# SchBTRC.net
KiCad netlist of a schematic drawn in Altium Designer
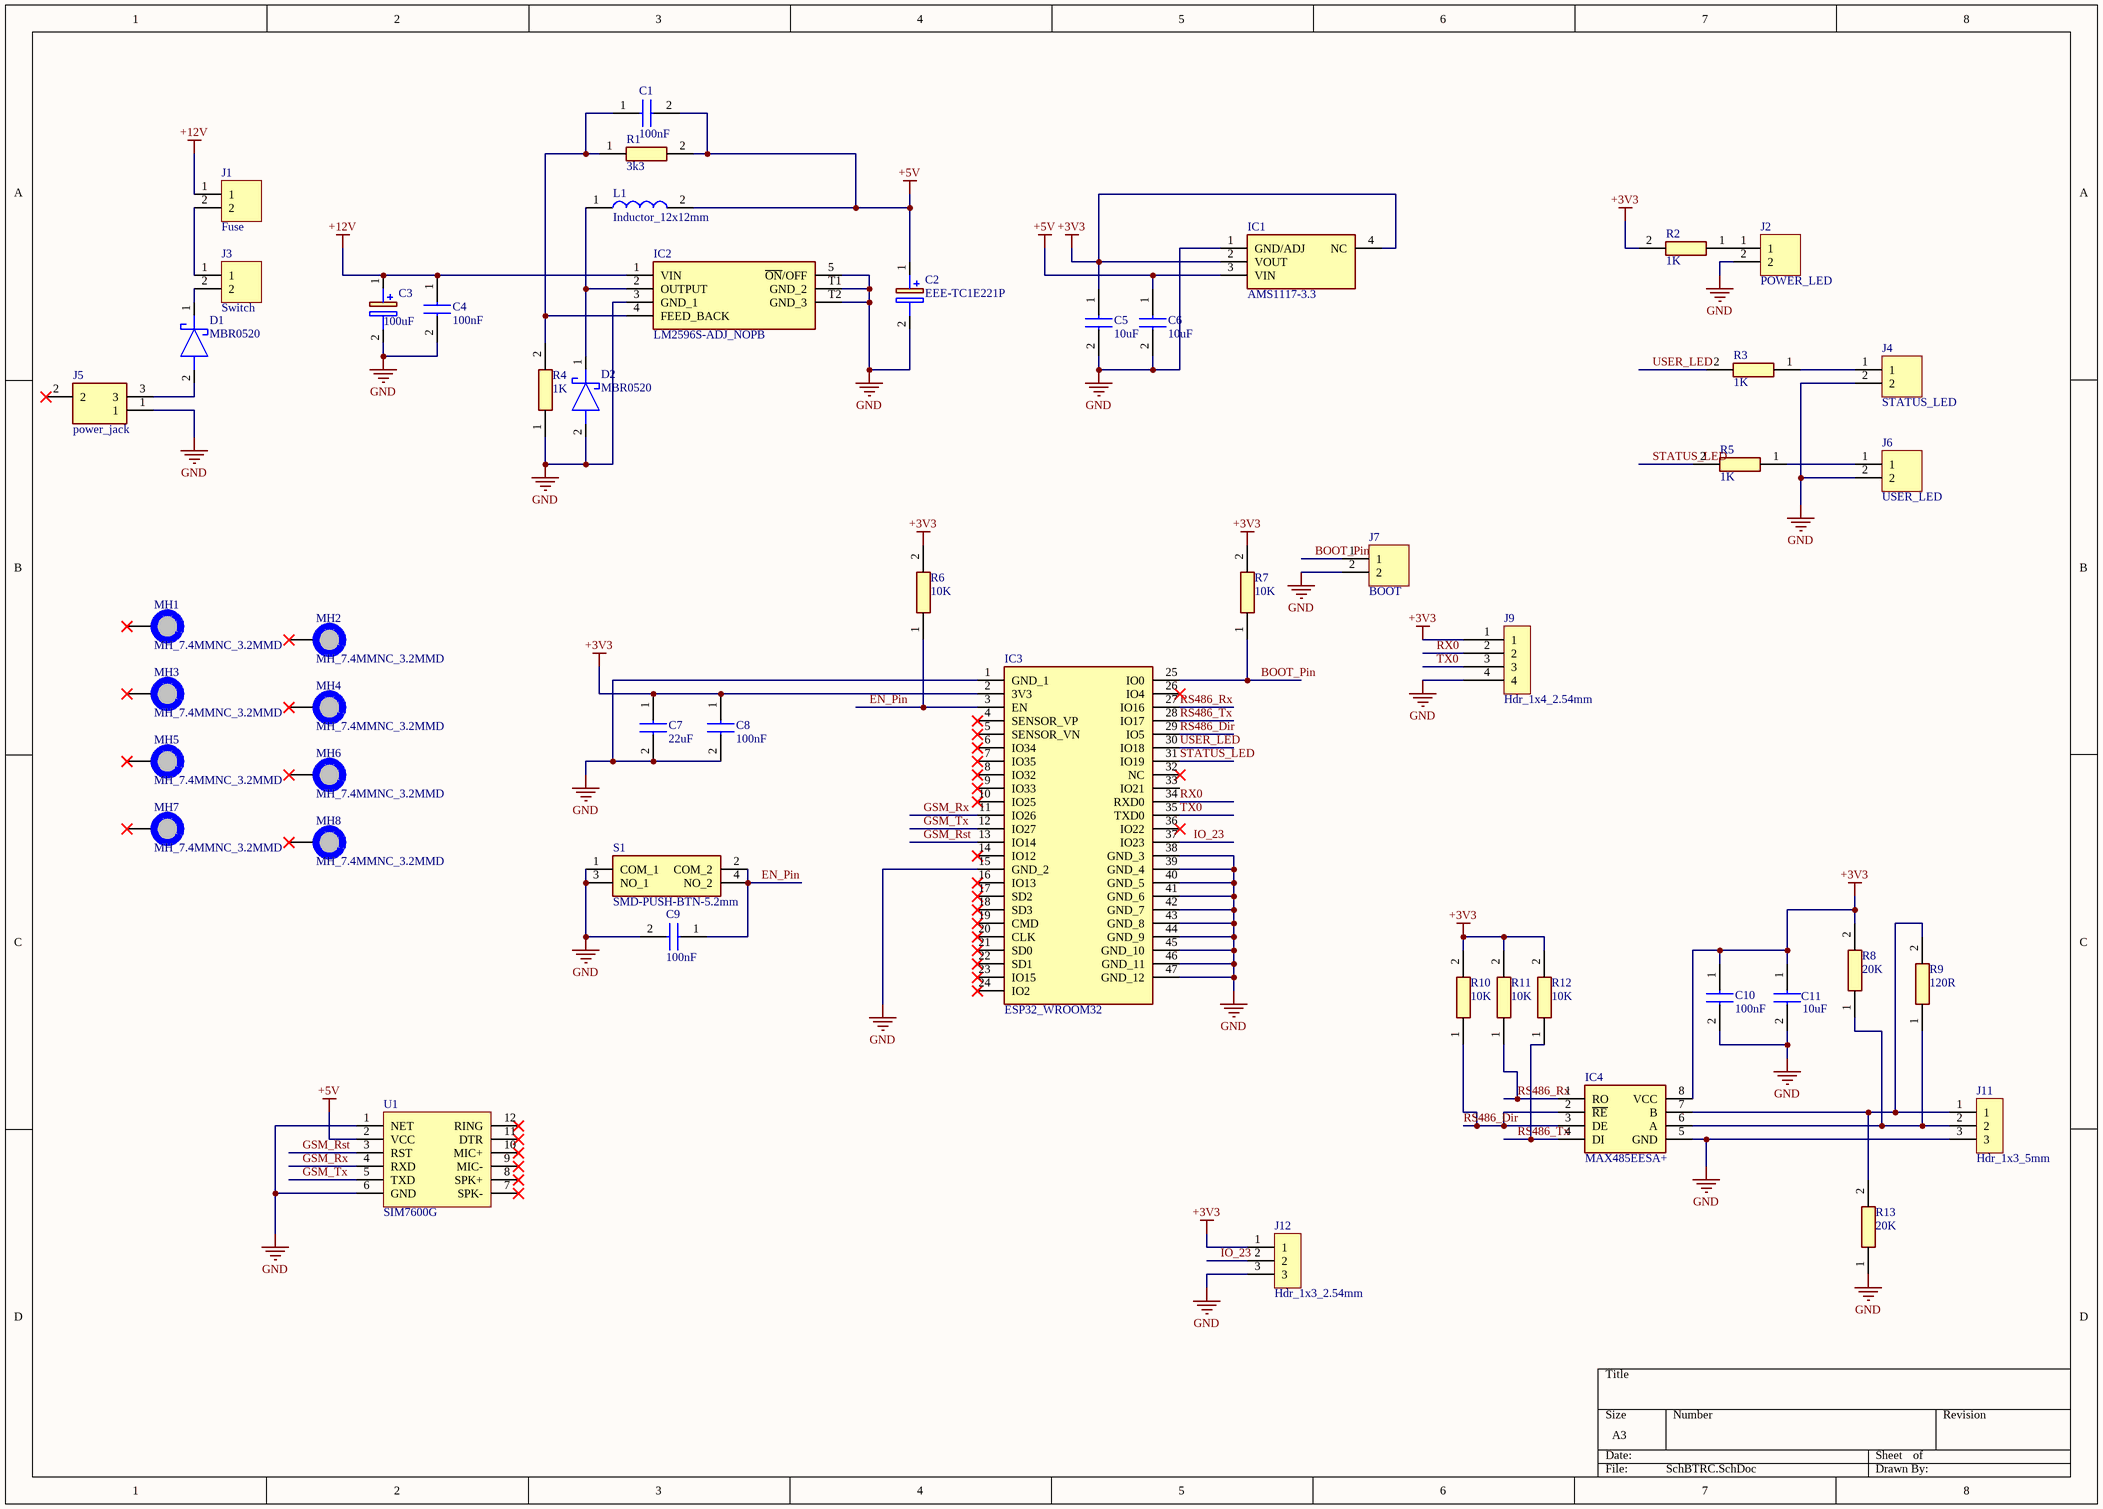
[diagram p0: SchBTRC.SchDoc]

(export (version "E")
  (design (tool "Eeschema 10.0.6"))
  (components
    (comp (ref "C1")
      (value "100nF")
      (footprint "CAPC3216X100N")
      (description "Capacitor")
      (fields
        (field (name "MANUFACTURER_PART_NUMBER") "C3216X5R1C106K085AC")
        (field (name "MOUSER PART NUMBER") "810-C3216X5R1C106K0C")
      )
      (libsource (lib "SchlibBTRC") (part "C3216X5R1C106K085AC"))
    )
    (comp (ref "C2")
      (value "EEE-TC1E221P")
      (footprint "PcbLibBTRC:EEE0JA152UAP")
      (description "Capacitor Polarised")
      (fields (field (name "MOUSER PART NUMBER") "667-EEE-TC1E221P"))
      (libsource (lib "*") (part "EEE-TC1E221P"))
    )
    (comp (ref "C3")
      (value "100uF")
      (footprint "PcbLibBTRC:EEE0JA331XP")
      (description "Capacitor Polarised")
      (fields
        (field (name "MANUFACTURER_PART_NUMBER") "EEE-TC1C101XP")
        (field (name "MOUSER PART NUMBER") "667-EEE-TC1C101XP")
      )
      (libsource (lib "*") (part "EEE-TC1C101XP"))
    )
    (comp (ref "C4")
      (value "100nF")
      (footprint "CAPC3216X100N")
      (description "Capacitor")
      (fields
        (field (name "MANUFACTURER_PART_NUMBER") "C3216X5R1C106K085AC")
        (field (name "MOUSER PART NUMBER") "810-C3216X5R1C106K0C")
      )
      (libsource (lib "SchlibBTRC") (part "C3216X5R1C106K085AC"))
    )
    (comp (ref "C5")
      (value "10uF")
      (footprint "CAPC3216X100N")
      (description "Capacitor")
      (fields
        (field (name "MANUFACTURER_PART_NUMBER") "C3216X5R1C106K085AC")
        (field (name "MOUSER PART NUMBER") "810-C3216X5R1C106K0C")
      )
      (libsource (lib "SchlibBTRC") (part "C3216X5R1C106K085AC"))
    )
    (comp (ref "C6")
      (value "10uF")
      (footprint "CAPC3216X100N")
      (description "Capacitor")
      (fields
        (field (name "MANUFACTURER_PART_NUMBER") "C3216X5R1C106K085AC")
        (field (name "MOUSER PART NUMBER") "810-C3216X5R1C106K0C")
      )
      (libsource (lib "SchlibBTRC") (part "C3216X5R1C106K085AC"))
    )
    (comp (ref "C7")
      (value "22uF")
      (footprint "CAPC3216X100N")
      (description "Capacitor")
      (fields
        (field (name "MANUFACTURER_PART_NUMBER") "C3216X5R1C106K085AC")
        (field (name "MOUSER PART NUMBER") "810-C3216X5R1C106K0C")
      )
      (libsource (lib "SchlibBTRC") (part "C3216X5R1C106K085AC"))
    )
    (comp (ref "C8")
      (value "100nF")
      (footprint "CAPC3216X100N")
      (description "Capacitor")
      (fields
        (field (name "MANUFACTURER_PART_NUMBER") "C3216X5R1C106K085AC")
        (field (name "MOUSER PART NUMBER") "810-C3216X5R1C106K0C")
      )
      (libsource (lib "SchlibBTRC") (part "C3216X5R1C106K085AC"))
    )
    (comp (ref "C9")
      (value "100nF")
      (footprint "CAPC3216X100N")
      (description "Capacitor")
      (fields
        (field (name "MANUFACTURER_PART_NUMBER") "C3216X5R1C106K085AC")
        (field (name "MOUSER PART NUMBER") "810-C3216X5R1C106K0C")
      )
      (libsource (lib "SchlibBTRC") (part "C3216X5R1C106K085AC"))
    )
    (comp (ref "C10")
      (value "100nF")
      (footprint "CAPC3216X100N")
      (description "Capacitor")
      (fields
        (field (name "MANUFACTURER_PART_NUMBER") "C3216X5R1C106K085AC")
        (field (name "MOUSER PART NUMBER") "810-C3216X5R1C106K0C")
      )
      (libsource (lib "SchlibBTRC") (part "C3216X5R1C106K085AC"))
    )
    (comp (ref "C11")
      (value "10uF")
      (footprint "CAPC3216X100N")
      (description "Capacitor")
      (fields
        (field (name "MANUFACTURER_PART_NUMBER") "C3216X5R1C106K085AC")
        (field (name "MOUSER PART NUMBER") "810-C3216X5R1C106K0C")
      )
      (libsource (lib "SchlibBTRC") (part "C3216X5R1C106K085AC"))
    )
    (comp (ref "D1")
      (value "MBR0520")
      (footprint "PcbLibBTRC:SOD3716X120N")
      (description "Schottky Diode")
      (libsource (lib "*") (part "MBR0520"))
    )
    (comp (ref "D2")
      (value "MBR0520")
      (footprint "PcbLibBTRC:SOD3716X120N")
      (description "Schottky Diode")
      (libsource (lib "*") (part "MBR0520"))
    )
    (comp (ref "IC1")
      (value "AMS1117-3.3")
      (footprint "PcbLibBTRC:SOT229P700X180-4N")
      (description "Integrated Circuit")
      (libsource (lib "*") (part "AMS1117-3.3"))
    )
    (comp (ref "IC2")
      (value "LM2596S-ADJ_NOPB")
      (footprint "PcbLibBTRC:LM2596SXADJ")
      (description "Integrated Circuit")
      (fields
        (field (name "MANUFACTURER_PART_NUMBER") "LM2596S-ADJ/NOPB")
        (field (name "MOUSER PART NUMBER") "926-LM2596S-ADJ/NOPB")
      )
      (libsource (lib "*") (part "LM2596S-ADJ_NOPB"))
    )
    (comp (ref "IC3")
      (value "ESP32_WROOM32")
      (footprint "PcbLibBTRC:ESP32WROOM32")
      (description "Integrated Circuit")
      (fields (field (name "MANUFACTURER_PART_NUMBER") "ESP32 WROOM32"))
      (libsource (lib "*") (part "ESP32_WROOM32"))
    )
    (comp (ref "IC4")
      (value "MAX485EESA+")
      (footprint "PcbLibBTRC:SOIC127P600X175-8N")
      (description "Integrated Circuit")
      (fields (field (name "MOUSER PART NUMBER") "700-MAX485EESA"))
      (libsource (lib "*") (part "MAX485EESA+"))
    )
    (comp (ref "J1")
      (value "Fuse")
      (footprint "HDR_1x2_2.54mm")
      (libsource (lib "SchlibBTRC") (part "Hdr_1x2_2.54mm"))
    )
    (comp (ref "J2")
      (value "POWER_LED")
      (footprint "HDR_1x2_2.54mm")
      (libsource (lib "SchlibBTRC") (part "Hdr_1x2_2.54mm"))
    )
    (comp (ref "J3")
      (value "Switch")
      (footprint "HDR_1x2_2.54mm")
      (libsource (lib "SchlibBTRC") (part "Hdr_1x2_2.54mm"))
    )
    (comp (ref "J4")
      (value "STATUS_LED")
      (footprint "HDR_1x2_2.54mm")
      (libsource (lib "SchlibBTRC") (part "Hdr_1x2_2.54mm"))
    )
    (comp (ref "J5")
      (value "power_jack")
      (footprint "power_jack")
      (description "Connector")
      (fields (field (name "MANUFACTURER_PART_NUMBER") "1613 20"))
      (libsource (lib "SchlibBTRC") (part "power_jack"))
    )
    (comp (ref "J6")
      (value "USER_LED")
      (footprint "HDR_1x2_2.54mm")
      (libsource (lib "SchlibBTRC") (part "Hdr_1x2_2.54mm"))
    )
    (comp (ref "J7")
      (value "BOOT")
      (footprint "HDR_1x2_2.54mm")
      (libsource (lib "SchlibBTRC") (part "Hdr_1x2_2.54mm"))
    )
    (comp (ref "J9")
      (value "Hdr_1x4_2.54mm")
      (footprint "Hdr_1x4_2.54mm")
      (libsource (lib "SchlibBTRC") (part "Hdr_1x4_2.54mm"))
    )
    (comp (ref "J11")
      (value "Hdr_1x3_5mm")
      (footprint "Hdr_1x3_5.0mm")
      (libsource (lib "SchlibBTRC") (part "Hdr_1x3_5mm"))
    )
    (comp (ref "J12")
      (value "Hdr_1x3_2.54mm")
      (footprint "Hdr_1x3_2.54mm")
      (libsource (lib "SchlibBTRC") (part "Hdr_1x3_2.54mm"))
    )
    (comp (ref "L1")
      (value "Inductor_12x12mm")
      (footprint "Inductor_12x12mm")
      (description "Inductor")
      (fields
        (field (name "MANUFACTURER_PART_NUMBER") "744774147")
        (field (name "MOUSER PART NUMBER") "710-744774147")
      )
      (libsource (lib "SchlibBTRC") (part "Inductor_12x12mm"))
    )
    (comp (ref "MH1")
      (value "MH_7.4MMNC_3.2MMD")
      (footprint "MH_7.4MMNC_3.2MMD_NON_COPPER_NPTH")
      (libsource (lib "SchlibBTRC") (part "MH_7.4MMNC_3.2MMD"))
    )
    (comp (ref "MH2")
      (value "MH_7.4MMNC_3.2MMD")
      (footprint "MH_7.4MMNC_3.2MMD_NON_COPPER_NPTH")
      (libsource (lib "SchlibBTRC") (part "MH_7.4MMNC_3.2MMD"))
    )
    (comp (ref "MH3")
      (value "MH_7.4MMNC_3.2MMD")
      (footprint "MH_7.4MMNC_3.2MMD_NON_COPPER_NPTH")
      (libsource (lib "SchlibBTRC") (part "MH_7.4MMNC_3.2MMD"))
    )
    (comp (ref "MH4")
      (value "MH_7.4MMNC_3.2MMD")
      (footprint "MH_7.4MMNC_3.2MMD_NON_COPPER_NPTH")
      (libsource (lib "SchlibBTRC") (part "MH_7.4MMNC_3.2MMD"))
    )
    (comp (ref "MH5")
      (value "MH_7.4MMNC_3.2MMD")
      (footprint "MH_7.4MMNC_3.2MMD_NON_COPPER_NPTH")
      (libsource (lib "SchlibBTRC") (part "MH_7.4MMNC_3.2MMD"))
    )
    (comp (ref "MH6")
      (value "MH_7.4MMNC_3.2MMD")
      (footprint "MH_7.4MMNC_3.2MMD_NON_COPPER_NPTH")
      (libsource (lib "SchlibBTRC") (part "MH_7.4MMNC_3.2MMD"))
    )
    (comp (ref "MH7")
      (value "MH_7.4MMNC_3.2MMD")
      (footprint "MH_7.4MMNC_3.2MMD_NON_COPPER_NPTH")
      (libsource (lib "SchlibBTRC") (part "MH_7.4MMNC_3.2MMD"))
    )
    (comp (ref "MH8")
      (value "MH_7.4MMNC_3.2MMD")
      (footprint "MH_7.4MMNC_3.2MMD_NON_COPPER_NPTH")
      (libsource (lib "SchlibBTRC") (part "MH_7.4MMNC_3.2MMD"))
    )
    (comp (ref "R1")
      (value "3k3")
      (footprint "RESC3216X75N")
      (description "Resistor")
      (fields
        (field (name "MANUFACTURER_PART_NUMBER") "CR1206-F/-2R00ELF")
        (field (name "MOUSER PART NUMBER") "652-CR1206-F/2R00ELF")
      )
      (libsource (lib "") (part "CR1206-F_-2R00ELF_2"))
    )
    (comp (ref "R2")
      (value "1K")
      (footprint "RESC3216X75N")
      (description "Resistor")
      (fields
        (field (name "MANUFACTURER_PART_NUMBER") "CR1206-F/-2R00ELF")
        (field (name "MOUSER PART NUMBER") "652-CR1206-F/2R00ELF")
      )
      (libsource (lib "") (part "CR1206-F_-2R00ELF_1"))
    )
    (comp (ref "R3")
      (value "1K")
      (footprint "RESC3216X75N")
      (description "Resistor")
      (fields
        (field (name "MANUFACTURER_PART_NUMBER") "CR1206-F/-2R00ELF")
        (field (name "MOUSER PART NUMBER") "652-CR1206-F/2R00ELF")
      )
      (libsource (lib "") (part "CR1206-F_-2R00ELF_1"))
    )
    (comp (ref "R4")
      (value "1K")
      (footprint "RESC3216X75N")
      (description "Resistor")
      (fields
        (field (name "MANUFACTURER_PART_NUMBER") "CR1206-F/-2R00ELF")
        (field (name "MOUSER PART NUMBER") "652-CR1206-F/2R00ELF")
      )
      (libsource (lib "SchlibBTRC") (part "CR1206-F_-2R00ELF"))
    )
    (comp (ref "R5")
      (value "1K")
      (footprint "RESC3216X75N")
      (description "Resistor")
      (fields
        (field (name "MANUFACTURER_PART_NUMBER") "CR1206-F/-2R00ELF")
        (field (name "MOUSER PART NUMBER") "652-CR1206-F/2R00ELF")
      )
      (libsource (lib "") (part "CR1206-F_-2R00ELF_1"))
    )
    (comp (ref "R6")
      (value "10K")
      (footprint "RESC3216X75N")
      (description "Resistor")
      (fields
        (field (name "MANUFACTURER_PART_NUMBER") "CR1206-F/-2R00ELF")
        (field (name "MOUSER PART NUMBER") "652-CR1206-F/2R00ELF")
      )
      (libsource (lib "SchlibBTRC") (part "CR1206-F_-2R00ELF"))
    )
    (comp (ref "R7")
      (value "10K")
      (footprint "RESC3216X75N")
      (description "Resistor")
      (fields
        (field (name "MANUFACTURER_PART_NUMBER") "CR1206-F/-2R00ELF")
        (field (name "MOUSER PART NUMBER") "652-CR1206-F/2R00ELF")
      )
      (libsource (lib "SchlibBTRC") (part "CR1206-F_-2R00ELF"))
    )
    (comp (ref "R8")
      (value "20K")
      (footprint "RESC3216X75N")
      (description "Resistor")
      (fields
        (field (name "MANUFACTURER_PART_NUMBER") "CR1206-F/-2R00ELF")
        (field (name "MOUSER PART NUMBER") "652-CR1206-F/2R00ELF")
      )
      (libsource (lib "SchlibBTRC") (part "CR1206-F_-2R00ELF"))
    )
    (comp (ref "R9")
      (value "120R")
      (footprint "RESC3216X75N")
      (description "Resistor")
      (fields
        (field (name "MANUFACTURER_PART_NUMBER") "CR1206-F/-2R00ELF")
        (field (name "MOUSER PART NUMBER") "652-CR1206-F/2R00ELF")
      )
      (libsource (lib "SchlibBTRC") (part "CR1206-F_-2R00ELF"))
    )
    (comp (ref "R10")
      (value "10K")
      (footprint "RESC3216X75N")
      (description "Resistor")
      (fields
        (field (name "MANUFACTURER_PART_NUMBER") "CR1206-F/-2R00ELF")
        (field (name "MOUSER PART NUMBER") "652-CR1206-F/2R00ELF")
      )
      (libsource (lib "SchlibBTRC") (part "CR1206-F_-2R00ELF"))
    )
    (comp (ref "R11")
      (value "10K")
      (footprint "RESC3216X75N")
      (description "Resistor")
      (fields
        (field (name "MANUFACTURER_PART_NUMBER") "CR1206-F/-2R00ELF")
        (field (name "MOUSER PART NUMBER") "652-CR1206-F/2R00ELF")
      )
      (libsource (lib "SchlibBTRC") (part "CR1206-F_-2R00ELF"))
    )
    (comp (ref "R12")
      (value "10K")
      (footprint "RESC3216X75N")
      (description "Resistor")
      (fields
        (field (name "MANUFACTURER_PART_NUMBER") "CR1206-F/-2R00ELF")
        (field (name "MOUSER PART NUMBER") "652-CR1206-F/2R00ELF")
      )
      (libsource (lib "SchlibBTRC") (part "CR1206-F_-2R00ELF"))
    )
    (comp (ref "R13")
      (value "20K")
      (footprint "RESC3216X75N")
      (description "Resistor")
      (fields
        (field (name "MANUFACTURER_PART_NUMBER") "CR1206-F/-2R00ELF")
        (field (name "MOUSER PART NUMBER") "652-CR1206-F/2R00ELF")
      )
      (libsource (lib "SchlibBTRC") (part "CR1206-F_-2R00ELF"))
    )
    (comp (ref "S1")
      (value "SMD-PUSH-BTN-5.2mm")
      (footprint "SMS_PUSH_BTN_5.2x5.2mm")
      (description "Switch")
      (fields
        (field (name "MANUFACTURER_PART_NUMBER") "COM-08720")
        (field (name "MOUSER PART NUMBER") "474-COM-08720")
      )
      (libsource (lib "SchlibBTRC") (part "SMD-PUSH-BTN-5.2mm"))
    )
    (comp (ref "U1")
      (value "SIM7600G")
      (footprint "SIM7600G_Module")
      (libsource (lib "SchlibBTRC") (part "SIM7600G_Module"))
    )
  )
  (nets
    (net (code "1") (name "+3V3") (class "Default")
      (node (ref "C10") (pin "1") (pinfunction "1_1") (pintype "passive"))
      (node (ref "C11") (pin "1") (pinfunction "1_1") (pintype "passive"))
      (node (ref "C5") (pin "1") (pinfunction "1_1") (pintype "passive"))
      (node (ref "C7") (pin "1") (pinfunction "1_1") (pintype "passive"))
      (node (ref "C8") (pin "1") (pinfunction "1_1") (pintype "passive"))
      (node (ref "IC1") (pin "2") (pinfunction "VOUT_2") (pintype "passive"))
      (node (ref "IC1") (pin "4") (pinfunction "NC_4") (pintype "passive"))
      (node (ref "IC3") (pin "2") (pinfunction "3V3_2") (pintype "passive"))
      (node (ref "IC4") (pin "8") (pinfunction "VCC_8") (pintype "passive"))
      (node (ref "J12") (pin "1") (pinfunction "1_1") (pintype "passive"))
      (node (ref "J9") (pin "1") (pinfunction "1_1") (pintype "passive"))
      (node (ref "R10") (pin "2") (pinfunction "2_2") (pintype "passive"))
      (node (ref "R11") (pin "2") (pinfunction "2_2") (pintype "passive"))
      (node (ref "R12") (pin "2") (pinfunction "2_2") (pintype "passive"))
      (node (ref "R2") (pin "2") (pinfunction "2_2") (pintype "passive"))
      (node (ref "R6") (pin "2") (pinfunction "2_2") (pintype "passive"))
      (node (ref "R7") (pin "2") (pinfunction "2_2") (pintype "passive"))
      (node (ref "R8") (pin "2") (pinfunction "2_2") (pintype "passive"))
    )
    (net (code "2") (name "+5V") (class "Default")
      (node (ref "C1") (pin "2") (pinfunction "2_2") (pintype "passive"))
      (node (ref "C2") (pin "1") (pinfunction "+_1") (pintype "passive"))
      (node (ref "C6") (pin "1") (pinfunction "1_1") (pintype "passive"))
      (node (ref "IC1") (pin "3") (pinfunction "VIN_3") (pintype "passive"))
      (node (ref "L1") (pin "2") (pinfunction "2_2") (pintype "passive"))
      (node (ref "R1") (pin "2") (pinfunction "2_2") (pintype "passive"))
      (node (ref "U1") (pin "2") (pinfunction "VCC_2") (pintype "passive"))
    )
    (net (code "3") (name "+12V") (class "Default")
      (node (ref "C3") (pin "1") (pinfunction "+_1") (pintype "passive"))
      (node (ref "C4") (pin "1") (pinfunction "1_1") (pintype "passive"))
      (node (ref "IC2") (pin "1") (pinfunction "VIN_1") (pintype "passive"))
      (node (ref "J1") (pin "1") (pinfunction "1_1") (pintype "passive"))
    )
    (net (code "4") (name "/BOOT_Pin") (class "Default")
      (node (ref "IC3") (pin "25") (pinfunction "IO0_25") (pintype "passive"))
      (node (ref "J7") (pin "1") (pinfunction "1_1") (pintype "passive"))
      (node (ref "R7") (pin "1") (pinfunction "1_1") (pintype "passive"))
    )
    (net (code "5") (name "/EN_Pin") (class "Default")
      (node (ref "C9") (pin "1") (pinfunction "1_1") (pintype "passive"))
      (node (ref "IC3") (pin "3") (pinfunction "EN_3") (pintype "passive"))
      (node (ref "R6") (pin "1") (pinfunction "1_1") (pintype "passive"))
      (node (ref "S1") (pin "2") (pinfunction "COM_2_2") (pintype "passive"))
      (node (ref "S1") (pin "4") (pinfunction "NO_2_4") (pintype "passive"))
    )
    (net (code "6") (name "/GSM_Rst") (class "Default")
      (node (ref "IC3") (pin "13") (pinfunction "IO14_13") (pintype "passive"))
      (node (ref "U1") (pin "3") (pinfunction "RST_3") (pintype "passive"))
    )
    (net (code "7") (name "/GSM_Rx") (class "Default")
      (node (ref "IC3") (pin "11") (pinfunction "IO26_11") (pintype "passive"))
      (node (ref "U1") (pin "4") (pinfunction "RXD_4") (pintype "passive"))
    )
    (net (code "8") (name "/GSM_Tx") (class "Default")
      (node (ref "IC3") (pin "12") (pinfunction "IO27_12") (pintype "passive"))
      (node (ref "U1") (pin "5") (pinfunction "TXD_5") (pintype "passive"))
    )
    (net (code "9") (name "/IO_23") (class "Default")
      (node (ref "IC3") (pin "37") (pinfunction "IO23_37") (pintype "passive"))
      (node (ref "J12") (pin "2") (pinfunction "2_2") (pintype "passive"))
    )
    (net (code "10") (name "/RS486_Dir") (class "Default")
      (node (ref "IC3") (pin "29") (pinfunction "IO5_29") (pintype "passive"))
      (node (ref "IC4") (pin "2") (pinfunction "~{RE}_2") (pintype "passive"))
      (node (ref "IC4") (pin "3") (pinfunction "DE_3") (pintype "passive"))
      (node (ref "R10") (pin "1") (pinfunction "1_1") (pintype "passive"))
    )
    (net (code "11") (name "/RS486_Rx") (class "Default")
      (node (ref "IC3") (pin "27") (pinfunction "IO16_27") (pintype "passive"))
      (node (ref "IC4") (pin "1") (pinfunction "RO_1") (pintype "passive"))
      (node (ref "R11") (pin "1") (pinfunction "1_1") (pintype "passive"))
    )
    (net (code "12") (name "/RS486_Tx") (class "Default")
      (node (ref "IC3") (pin "28") (pinfunction "IO17_28") (pintype "passive"))
      (node (ref "IC4") (pin "4") (pinfunction "DI_4") (pintype "passive"))
      (node (ref "R12") (pin "1") (pinfunction "1_1") (pintype "passive"))
    )
    (net (code "13") (name "/RX0") (class "Default")
      (node (ref "IC3") (pin "34") (pinfunction "RXD0_34") (pintype "passive"))
      (node (ref "J9") (pin "2") (pinfunction "2_2") (pintype "passive"))
    )
    (net (code "14") (name "/STATUS_LED") (class "Default")
      (node (ref "IC3") (pin "31") (pinfunction "IO19_31") (pintype "passive"))
      (node (ref "R5") (pin "2") (pinfunction "2_2") (pintype "passive"))
    )
    (net (code "15") (name "/TX0") (class "Default")
      (node (ref "IC3") (pin "35") (pinfunction "TXD0_35") (pintype "passive"))
      (node (ref "J9") (pin "3") (pinfunction "3_3") (pintype "passive"))
    )
    (net (code "16") (name "/USER_LED") (class "Default")
      (node (ref "IC3") (pin "30") (pinfunction "IO18_30") (pintype "passive"))
      (node (ref "R3") (pin "2") (pinfunction "2_2") (pintype "passive"))
    )
    (net (code "17") (name "GND") (class "Default")
      (node (ref "C10") (pin "2") (pinfunction "2_2") (pintype "passive"))
      (node (ref "C11") (pin "2") (pinfunction "2_2") (pintype "passive"))
      (node (ref "C2") (pin "2") (pinfunction "-_2") (pintype "passive"))
      (node (ref "C3") (pin "2") (pinfunction "-_2") (pintype "passive"))
      (node (ref "C4") (pin "2") (pinfunction "2_2") (pintype "passive"))
      (node (ref "C5") (pin "2") (pinfunction "2_2") (pintype "passive"))
      (node (ref "C6") (pin "2") (pinfunction "2_2") (pintype "passive"))
      (node (ref "C7") (pin "2") (pinfunction "2_2") (pintype "passive"))
      (node (ref "C8") (pin "2") (pinfunction "2_2") (pintype "passive"))
      (node (ref "C9") (pin "2") (pinfunction "2_2") (pintype "passive"))
      (node (ref "D2") (pin "2") (pinfunction "A_2") (pintype "passive"))
      (node (ref "IC1") (pin "1") (pinfunction "GND/ADJ_1") (pintype "passive"))
      (node (ref "IC2") (pin "3") (pinfunction "GND_1_3") (pintype "passive"))
      (node (ref "IC2") (pin "5") (pinfunction "~{ON}/OFF_5") (pintype "passive"))
      (node (ref "IC2") (pin "T1") (pinfunction "GND_2_T1") (pintype "passive"))
      (node (ref "IC2") (pin "T2") (pinfunction "GND_3_T2") (pintype "passive"))
      (node (ref "IC3") (pin "1") (pinfunction "GND_1_1") (pintype "passive"))
      (node (ref "IC3") (pin "15") (pinfunction "GND_2_15") (pintype "passive"))
      (node (ref "IC3") (pin "38") (pinfunction "GND_3_38") (pintype "passive"))
      (node (ref "IC3") (pin "39") (pinfunction "GND_4_39") (pintype "passive"))
      (node (ref "IC3") (pin "40") (pinfunction "GND_5_40") (pintype "passive"))
      (node (ref "IC3") (pin "41") (pinfunction "GND_6_41") (pintype "passive"))
      (node (ref "IC3") (pin "42") (pinfunction "GND_7_42") (pintype "passive"))
      (node (ref "IC3") (pin "43") (pinfunction "GND_8_43") (pintype "passive"))
      (node (ref "IC3") (pin "44") (pinfunction "GND_9_44") (pintype "passive"))
      (node (ref "IC3") (pin "45") (pinfunction "GND_10_45") (pintype "passive"))
      (node (ref "IC3") (pin "46") (pinfunction "GND_11_46") (pintype "passive"))
      (node (ref "IC3") (pin "47") (pinfunction "GND_12_47") (pintype "passive"))
      (node (ref "IC4") (pin "5") (pinfunction "GND_5") (pintype "passive"))
      (node (ref "J11") (pin "3") (pinfunction "3_3") (pintype "passive"))
      (node (ref "J12") (pin "3") (pinfunction "3_3") (pintype "passive"))
      (node (ref "J2") (pin "2") (pinfunction "2_2") (pintype "passive"))
      (node (ref "J4") (pin "2") (pinfunction "2_2") (pintype "passive"))
      (node (ref "J5") (pin "1") (pinfunction "1_1") (pintype "passive"))
      (node (ref "J6") (pin "2") (pinfunction "2_2") (pintype "passive"))
      (node (ref "J7") (pin "2") (pinfunction "2_2") (pintype "passive"))
      (node (ref "J9") (pin "4") (pinfunction "4_4") (pintype "passive"))
      (node (ref "R13") (pin "1") (pinfunction "1_1") (pintype "passive"))
      (node (ref "R4") (pin "1") (pinfunction "1_1") (pintype "passive"))
      (node (ref "S1") (pin "1") (pinfunction "COM_1_1") (pintype "passive"))
      (node (ref "S1") (pin "3") (pinfunction "NO_1_3") (pintype "passive"))
      (node (ref "U1") (pin "1") (pinfunction "NET_1") (pintype "passive"))
      (node (ref "U1") (pin "6") (pinfunction "GND_6") (pintype "passive"))
    )
    (net (code "18") (name "Net-(D1-A)") (class "Default")
      (node (ref "D1") (pin "2") (pinfunction "A_2") (pintype "passive"))
      (node (ref "J5") (pin "3") (pinfunction "3_3") (pintype "passive"))
    )
    (net (code "19") (name "Net-(D1-K)") (class "Default")
      (node (ref "D1") (pin "1") (pinfunction "K_1") (pintype "passive"))
      (node (ref "J3") (pin "2") (pinfunction "2_2") (pintype "passive"))
    )
    (net (code "20") (name "Net-(D2-K)") (class "Default")
      (node (ref "D2") (pin "1") (pinfunction "K_1") (pintype "passive"))
      (node (ref "IC2") (pin "2") (pinfunction "OUTPUT_2") (pintype "passive"))
      (node (ref "L1") (pin "1") (pinfunction "1_1") (pintype "passive"))
    )
    (net (code "21") (name "Net-(IC2-FEED_BACK)") (class "Default")
      (node (ref "C1") (pin "1") (pinfunction "1_1") (pintype "passive"))
      (node (ref "IC2") (pin "4") (pinfunction "FEED_BACK_4") (pintype "passive"))
      (node (ref "R1") (pin "1") (pinfunction "1_1") (pintype "passive"))
      (node (ref "R4") (pin "2") (pinfunction "2_2") (pintype "passive"))
    )
    (net (code "22") (name "Net-(IC4-A)") (class "Default")
      (node (ref "IC4") (pin "6") (pinfunction "A_6") (pintype "passive"))
      (node (ref "J11") (pin "2") (pinfunction "2_2") (pintype "passive"))
      (node (ref "R8") (pin "1") (pinfunction "1_1") (pintype "passive"))
      (node (ref "R9") (pin "1") (pinfunction "1_1") (pintype "passive"))
    )
    (net (code "23") (name "Net-(IC4-B)") (class "Default")
      (node (ref "IC4") (pin "7") (pinfunction "B_7") (pintype "passive"))
      (node (ref "J11") (pin "1") (pinfunction "1_1") (pintype "passive"))
      (node (ref "R13") (pin "2") (pinfunction "2_2") (pintype "passive"))
      (node (ref "R9") (pin "2") (pinfunction "2_2") (pintype "passive"))
    )
    (net (code "24") (name "Net-(J1-Pad2)") (class "Default")
      (node (ref "J1") (pin "2") (pinfunction "2_2") (pintype "passive"))
      (node (ref "J3") (pin "1") (pinfunction "1_1") (pintype "passive"))
    )
    (net (code "25") (name "Net-(J2-Pad1)") (class "Default")
      (node (ref "J2") (pin "1") (pinfunction "1_1") (pintype "passive"))
      (node (ref "R2") (pin "1") (pinfunction "1_1") (pintype "passive"))
    )
    (net (code "26") (name "Net-(J4-Pad1)") (class "Default")
      (node (ref "J4") (pin "1") (pinfunction "1_1") (pintype "passive"))
      (node (ref "R3") (pin "1") (pinfunction "1_1") (pintype "passive"))
    )
    (net (code "27") (name "Net-(J6-Pad1)") (class "Default")
      (node (ref "J6") (pin "1") (pinfunction "1_1") (pintype "passive"))
      (node (ref "R5") (pin "1") (pinfunction "1_1") (pintype "passive"))
    )
    (net (code "28") (name "unconnected-(IC3-CLK-Pad20)") (class "Default")
      (node (ref "IC3") (pin "20") (pinfunction "CLK_20") (pintype "passive+no_connect"))
    )
    (net (code "29") (name "unconnected-(IC3-CMD-Pad19)") (class "Default")
      (node (ref "IC3") (pin "19") (pinfunction "CMD_19") (pintype "passive+no_connect"))
    )
    (net (code "30") (name "unconnected-(IC3-IO2-Pad24)") (class "Default")
      (node (ref "IC3") (pin "24") (pinfunction "IO2_24") (pintype "passive+no_connect"))
    )
    (net (code "31") (name "unconnected-(IC3-IO4-Pad26)") (class "Default")
      (node (ref "IC3") (pin "26") (pinfunction "IO4_26") (pintype "passive+no_connect"))
    )
    (net (code "32") (name "unconnected-(IC3-IO12-Pad14)") (class "Default")
      (node (ref "IC3") (pin "14") (pinfunction "IO12_14") (pintype "passive+no_connect"))
    )
    (net (code "33") (name "unconnected-(IC3-IO13-Pad16)") (class "Default")
      (node (ref "IC3") (pin "16") (pinfunction "IO13_16") (pintype "passive+no_connect"))
    )
    (net (code "34") (name "unconnected-(IC3-IO15-Pad23)") (class "Default")
      (node (ref "IC3") (pin "23") (pinfunction "IO15_23") (pintype "passive+no_connect"))
    )
    (net (code "35") (name "unconnected-(IC3-IO21-Pad33)") (class "Default")
      (node (ref "IC3") (pin "33") (pinfunction "IO21_33") (pintype "passive"))
    )
    (net (code "36") (name "unconnected-(IC3-IO22-Pad36)") (class "Default")
      (node (ref "IC3") (pin "36") (pinfunction "IO22_36") (pintype "passive+no_connect"))
    )
    (net (code "37") (name "unconnected-(IC3-IO25-Pad10)") (class "Default")
      (node (ref "IC3") (pin "10") (pinfunction "IO25_10") (pintype "passive+no_connect"))
    )
    (net (code "38") (name "unconnected-(IC3-IO32-Pad8)") (class "Default")
      (node (ref "IC3") (pin "8") (pinfunction "IO32_8") (pintype "passive+no_connect"))
    )
    (net (code "39") (name "unconnected-(IC3-IO33-Pad9)") (class "Default")
      (node (ref "IC3") (pin "9") (pinfunction "IO33_9") (pintype "passive+no_connect"))
    )
    (net (code "40") (name "unconnected-(IC3-IO34-Pad6)") (class "Default")
      (node (ref "IC3") (pin "6") (pinfunction "IO34_6") (pintype "passive+no_connect"))
    )
    (net (code "41") (name "unconnected-(IC3-IO35-Pad7)") (class "Default")
      (node (ref "IC3") (pin "7") (pinfunction "IO35_7") (pintype "passive+no_connect"))
    )
    (net (code "42") (name "unconnected-(IC3-NC-Pad32)") (class "Default")
      (node (ref "IC3") (pin "32") (pinfunction "NC_32") (pintype "passive+no_connect"))
    )
    (net (code "43") (name "unconnected-(IC3-SD0-Pad21)") (class "Default")
      (node (ref "IC3") (pin "21") (pinfunction "SD0_21") (pintype "passive+no_connect"))
    )
    (net (code "44") (name "unconnected-(IC3-SD1-Pad22)") (class "Default")
      (node (ref "IC3") (pin "22") (pinfunction "SD1_22") (pintype "passive+no_connect"))
    )
    (net (code "45") (name "unconnected-(IC3-SD2-Pad17)") (class "Default")
      (node (ref "IC3") (pin "17") (pinfunction "SD2_17") (pintype "passive+no_connect"))
    )
    (net (code "46") (name "unconnected-(IC3-SD3-Pad18)") (class "Default")
      (node (ref "IC3") (pin "18") (pinfunction "SD3_18") (pintype "passive+no_connect"))
    )
    (net (code "47") (name "unconnected-(IC3-SENSOR_VN-Pad5)") (class "Default")
      (node (ref "IC3") (pin "5") (pinfunction "SENSOR_VN_5") (pintype "passive+no_connect"))
    )
    (net (code "48") (name "unconnected-(IC3-SENSOR_VP-Pad4)") (class "Default")
      (node (ref "IC3") (pin "4") (pinfunction "SENSOR_VP_4") (pintype "passive+no_connect"))
    )
    (net (code "49") (name "unconnected-(J5-Pad2)") (class "Default")
      (node (ref "J5") (pin "2") (pinfunction "2_2") (pintype "passive+no_connect"))
    )
    (net (code "50") (name "unconnected-(MH1-Pad1)") (class "Default")
      (node (ref "MH1") (pin "1") (pinfunction "1_1") (pintype "passive+no_connect"))
    )
    (net (code "51") (name "unconnected-(MH2-Pad1)") (class "Default")
      (node (ref "MH2") (pin "1") (pinfunction "1_1") (pintype "passive+no_connect"))
    )
    (net (code "52") (name "unconnected-(MH3-Pad1)") (class "Default")
      (node (ref "MH3") (pin "1") (pinfunction "1_1") (pintype "passive+no_connect"))
    )
    (net (code "53") (name "unconnected-(MH4-Pad1)") (class "Default")
      (node (ref "MH4") (pin "1") (pinfunction "1_1") (pintype "passive+no_connect"))
    )
    (net (code "54") (name "unconnected-(MH5-Pad1)") (class "Default")
      (node (ref "MH5") (pin "1") (pinfunction "1_1") (pintype "passive+no_connect"))
    )
    (net (code "55") (name "unconnected-(MH6-Pad1)") (class "Default")
      (node (ref "MH6") (pin "1") (pinfunction "1_1") (pintype "passive+no_connect"))
    )
    (net (code "56") (name "unconnected-(MH7-Pad1)") (class "Default")
      (node (ref "MH7") (pin "1") (pinfunction "1_1") (pintype "passive+no_connect"))
    )
    (net (code "57") (name "unconnected-(MH8-Pad1)") (class "Default")
      (node (ref "MH8") (pin "1") (pinfunction "1_1") (pintype "passive+no_connect"))
    )
    (net (code "58") (name "unconnected-(U1-DTR-Pad11)") (class "Default")
      (node (ref "U1") (pin "11") (pinfunction "DTR_11") (pintype "passive+no_connect"))
    )
    (net (code "59") (name "unconnected-(U1-MIC+-Pad10)") (class "Default")
      (node (ref "U1") (pin "10") (pinfunction "MIC+_10") (pintype "passive+no_connect"))
    )
    (net (code "60") (name "unconnected-(U1-MIC--Pad9)") (class "Default")
      (node (ref "U1") (pin "9") (pinfunction "MIC-_9") (pintype "passive+no_connect"))
    )
    (net (code "61") (name "unconnected-(U1-RING-Pad12)") (class "Default")
      (node (ref "U1") (pin "12") (pinfunction "RING_12") (pintype "passive+no_connect"))
    )
    (net (code "62") (name "unconnected-(U1-SPK+-Pad8)") (class "Default")
      (node (ref "U1") (pin "8") (pinfunction "SPK+_8") (pintype "passive+no_connect"))
    )
    (net (code "63") (name "unconnected-(U1-SPK--Pad7)") (class "Default")
      (node (ref "U1") (pin "7") (pinfunction "SPK-_7") (pintype "passive+no_connect"))
    )
  )
)
